# display_board.net
KiCad netlist of a schematic drawn in EasyEDA
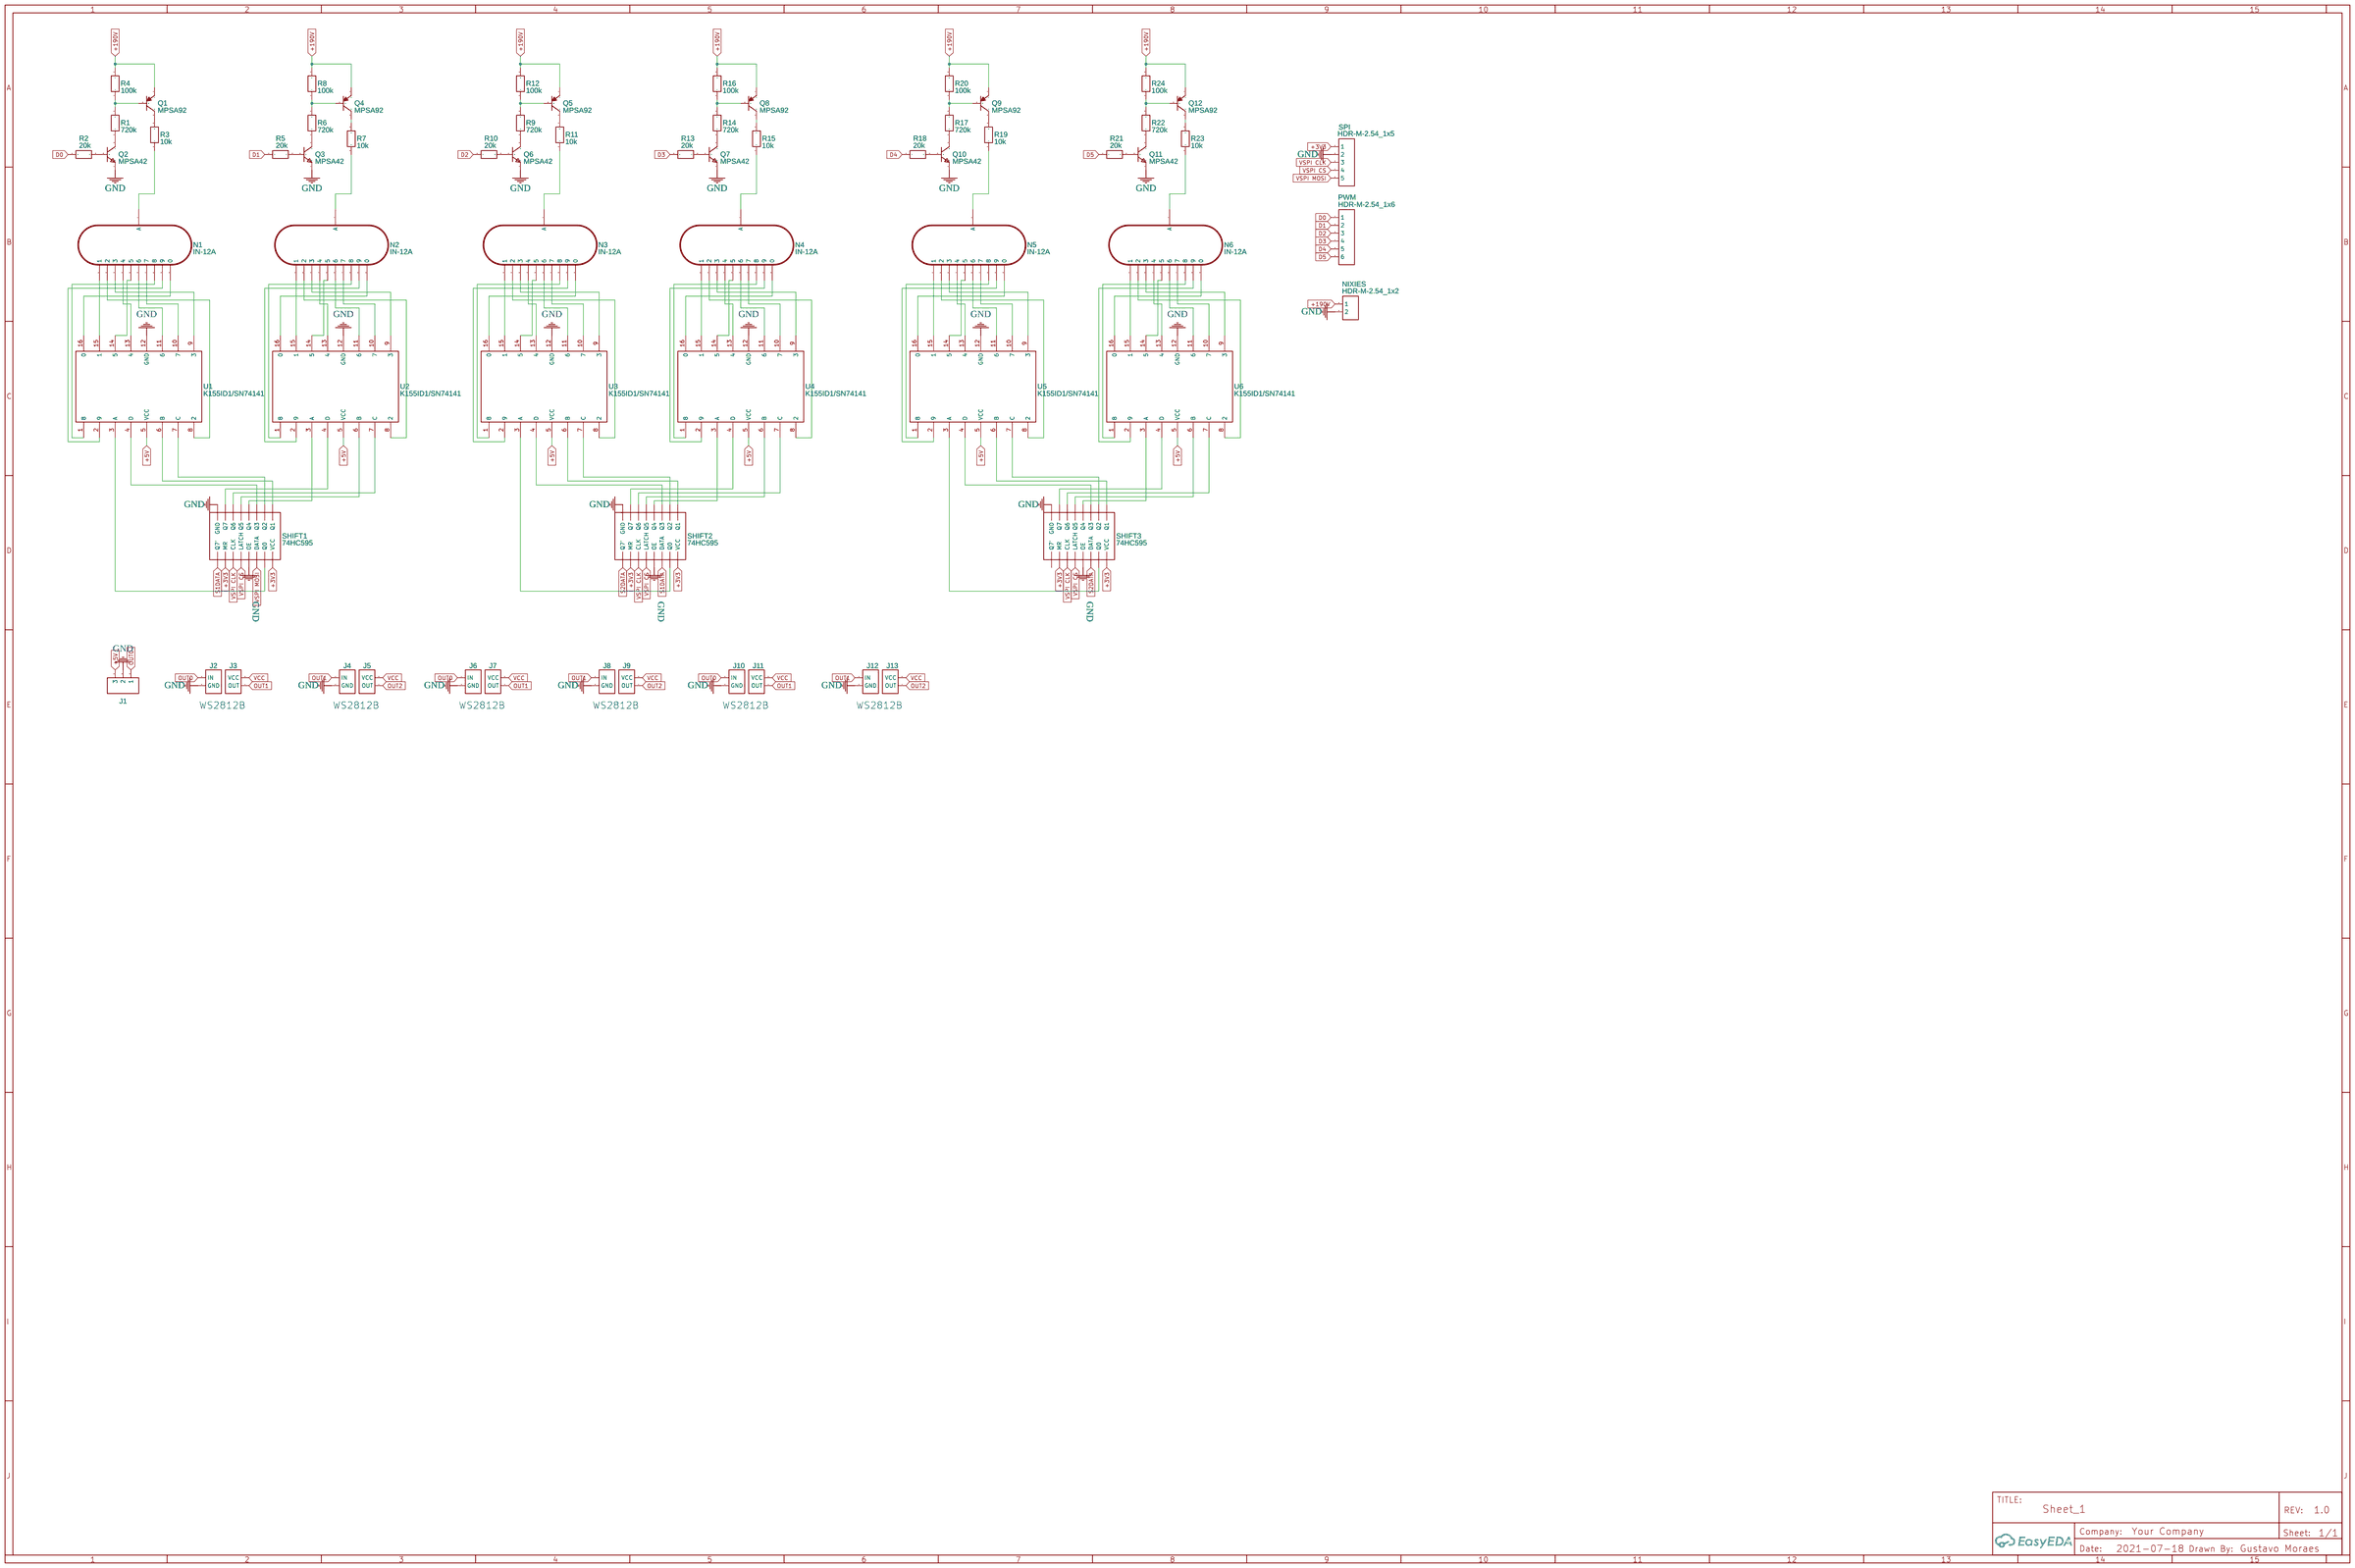
[diagram p0: schematic sheet]

(export (version "E")
  (design (tool "Eeschema 10.0.6"))
  (components
    (comp (ref "J1")
      (value "HDR-M-2.54_1x3")
      (fields (field (name "BOM_Supplier Part") "C180248"))
      (libsource (lib "") (part "HDR-M-2.54_1x3"))
    )
    (comp (ref "J2")
      (value "HDR-M-2.54_1x2")
      (fields (field (name "BOM_Supplier Part") "C124375"))
      (libsource (lib "") (part "HDR-M-2.54_1x2"))
    )
    (comp (ref "J3")
      (value "HDR-M-2.54_1x2")
      (fields (field (name "BOM_Supplier Part") "C124375"))
      (libsource (lib "") (part "HDR-M-2.54_1x2_1"))
    )
    (comp (ref "J4")
      (value "HDR-M-2.54_1x2")
      (fields (field (name "BOM_Supplier Part") "C124375"))
      (libsource (lib "") (part "HDR-M-2.54_1x2"))
    )
    (comp (ref "J5")
      (value "HDR-M-2.54_1x2")
      (fields (field (name "BOM_Supplier Part") "C124375"))
      (libsource (lib "") (part "HDR-M-2.54_1x2_1"))
    )
    (comp (ref "J6")
      (value "HDR-M-2.54_1x2")
      (fields (field (name "BOM_Supplier Part") "C124375"))
      (libsource (lib "") (part "HDR-M-2.54_1x2"))
    )
    (comp (ref "J7")
      (value "HDR-M-2.54_1x2")
      (fields (field (name "BOM_Supplier Part") "C124375"))
      (libsource (lib "") (part "HDR-M-2.54_1x2_1"))
    )
    (comp (ref "J8")
      (value "HDR-M-2.54_1x2")
      (fields (field (name "BOM_Supplier Part") "C124375"))
      (libsource (lib "") (part "HDR-M-2.54_1x2"))
    )
    (comp (ref "J9")
      (value "HDR-M-2.54_1x2")
      (fields (field (name "BOM_Supplier Part") "C124375"))
      (libsource (lib "") (part "HDR-M-2.54_1x2_1"))
    )
    (comp (ref "J10")
      (value "HDR-M-2.54_1x2")
      (fields (field (name "BOM_Supplier Part") "C124375"))
      (libsource (lib "") (part "HDR-M-2.54_1x2"))
    )
    (comp (ref "J11")
      (value "HDR-M-2.54_1x2")
      (fields (field (name "BOM_Supplier Part") "C124375"))
      (libsource (lib "") (part "HDR-M-2.54_1x2_1"))
    )
    (comp (ref "J12")
      (value "HDR-M-2.54_1x2")
      (fields (field (name "BOM_Supplier Part") "C124375"))
      (libsource (lib "") (part "HDR-M-2.54_1x2"))
    )
    (comp (ref "J13")
      (value "HDR-M-2.54_1x2")
      (fields (field (name "BOM_Supplier Part") "C124375"))
      (libsource (lib "") (part "HDR-M-2.54_1x2_1"))
    )
    (comp (ref "N1") (value "IN-12A") (libsource (lib "") (part "IN-12A")))
    (comp (ref "N2") (value "IN-12A") (libsource (lib "") (part "IN-12A")))
    (comp (ref "N3") (value "IN-12A") (libsource (lib "") (part "IN-12A")))
    (comp (ref "N4") (value "IN-12A") (libsource (lib "") (part "IN-12A")))
    (comp (ref "N5") (value "IN-12A") (libsource (lib "") (part "IN-12A")))
    (comp (ref "N6") (value "IN-12A") (libsource (lib "") (part "IN-12A")))
    (comp (ref "NIXIES")
      (value "HDR-M-2.54_1x2")
      (fields (field (name "BOM_Supplier Part") "C124375"))
      (libsource (lib "") (part "HDR-M-2.54_1x2_2"))
    )
    (comp (ref "PWM")
      (value "HDR-M-2.54_1x6")
      (fields (field (name "BOM_Supplier Part") "C190819"))
      (libsource (lib "") (part "HDR-M-2.54_1x6"))
    )
    (comp (ref "Q1")
      (value "MPSA92")
      (fields (field (name "BOM_Supplier Part") "C118558"))
      (libsource (lib "") (part "MPSA92"))
    )
    (comp (ref "Q2")
      (value "MPSA42")
      (fields (field (name "BOM_Supplier Part") "C118557"))
      (libsource (lib "") (part "MPSA42"))
    )
    (comp (ref "Q3")
      (value "MPSA42")
      (fields (field (name "BOM_Supplier Part") "C118557"))
      (libsource (lib "") (part "MPSA42"))
    )
    (comp (ref "Q4")
      (value "MPSA92")
      (fields (field (name "BOM_Supplier Part") "C118558"))
      (libsource (lib "") (part "MPSA92"))
    )
    (comp (ref "Q5")
      (value "MPSA92")
      (fields (field (name "BOM_Supplier Part") "C118558"))
      (libsource (lib "") (part "MPSA92"))
    )
    (comp (ref "Q6")
      (value "MPSA42")
      (fields (field (name "BOM_Supplier Part") "C118557"))
      (libsource (lib "") (part "MPSA42"))
    )
    (comp (ref "Q7")
      (value "MPSA42")
      (fields (field (name "BOM_Supplier Part") "C118557"))
      (libsource (lib "") (part "MPSA42"))
    )
    (comp (ref "Q8")
      (value "MPSA92")
      (fields (field (name "BOM_Supplier Part") "C118558"))
      (libsource (lib "") (part "MPSA92"))
    )
    (comp (ref "Q9")
      (value "MPSA92")
      (fields (field (name "BOM_Supplier Part") "C118558"))
      (libsource (lib "") (part "MPSA92"))
    )
    (comp (ref "Q10")
      (value "MPSA42")
      (fields (field (name "BOM_Supplier Part") "C118557"))
      (libsource (lib "") (part "MPSA42"))
    )
    (comp (ref "Q11")
      (value "MPSA42")
      (fields (field (name "BOM_Supplier Part") "C118557"))
      (libsource (lib "") (part "MPSA42"))
    )
    (comp (ref "Q12")
      (value "MPSA92")
      (fields (field (name "BOM_Supplier Part") "C118558"))
      (libsource (lib "") (part "MPSA92"))
    )
    (comp (ref "R1") (value "720k") (libsource (lib "") (part "R_AXIAL-0.3_EU")))
    (comp (ref "R2") (value "20k") (libsource (lib "") (part "R_AXIAL-0.3_EU_1")))
    (comp (ref "R3") (value "10k") (libsource (lib "") (part "R_AXIAL-0.3_EU")))
    (comp (ref "R4") (value "100k") (libsource (lib "") (part "R_AXIAL-0.3_EU")))
    (comp (ref "R5") (value "20k") (libsource (lib "") (part "R_AXIAL-0.3_EU_1")))
    (comp (ref "R6") (value "720k") (libsource (lib "") (part "R_AXIAL-0.3_EU")))
    (comp (ref "R7") (value "10k") (libsource (lib "") (part "R_AXIAL-0.3_EU")))
    (comp (ref "R8") (value "100k") (libsource (lib "") (part "R_AXIAL-0.3_EU")))
    (comp (ref "R9") (value "720k") (libsource (lib "") (part "R_AXIAL-0.3_EU")))
    (comp (ref "R10") (value "20k") (libsource (lib "") (part "R_AXIAL-0.3_EU_1")))
    (comp (ref "R11") (value "10k") (libsource (lib "") (part "R_AXIAL-0.3_EU")))
    (comp (ref "R12") (value "100k") (libsource (lib "") (part "R_AXIAL-0.3_EU")))
    (comp (ref "R13") (value "20k") (libsource (lib "") (part "R_AXIAL-0.3_EU_1")))
    (comp (ref "R14") (value "720k") (libsource (lib "") (part "R_AXIAL-0.3_EU")))
    (comp (ref "R15") (value "10k") (libsource (lib "") (part "R_AXIAL-0.3_EU")))
    (comp (ref "R16") (value "100k") (libsource (lib "") (part "R_AXIAL-0.3_EU")))
    (comp (ref "R17") (value "720k") (libsource (lib "") (part "R_AXIAL-0.3_EU")))
    (comp (ref "R18") (value "20k") (libsource (lib "") (part "R_AXIAL-0.3_EU_1")))
    (comp (ref "R19") (value "10k") (libsource (lib "") (part "R_AXIAL-0.3_EU")))
    (comp (ref "R20") (value "100k") (libsource (lib "") (part "R_AXIAL-0.3_EU")))
    (comp (ref "R21") (value "20k") (libsource (lib "") (part "R_AXIAL-0.3_EU_1")))
    (comp (ref "R22") (value "720k") (libsource (lib "") (part "R_AXIAL-0.3_EU")))
    (comp (ref "R23") (value "10k") (libsource (lib "") (part "R_AXIAL-0.3_EU")))
    (comp (ref "R24") (value "100k") (libsource (lib "") (part "R_AXIAL-0.3_EU")))
    (comp (ref "SHIFT1") (value "74HC595") (libsource (lib "") (part "74HC595")))
    (comp (ref "SHIFT2") (value "74HC595") (libsource (lib "") (part "74HC595")))
    (comp (ref "SHIFT3") (value "74HC595") (libsource (lib "") (part "74HC595")))
    (comp (ref "SPI")
      (value "HDR-M-2.54_1x5")
      (fields (field (name "BOM_Supplier Part") "C358687"))
      (libsource (lib "") (part "HDR-M-2.54_1x5"))
    )
    (comp (ref "U1") (value "K155ID1/SN74141") (libsource (lib "") (part "K155ID1/SN74141")))
    (comp (ref "U2") (value "K155ID1/SN74141") (libsource (lib "") (part "K155ID1/SN74141")))
    (comp (ref "U3") (value "K155ID1/SN74141") (libsource (lib "") (part "K155ID1/SN74141")))
    (comp (ref "U4") (value "K155ID1/SN74141") (libsource (lib "") (part "K155ID1/SN74141")))
    (comp (ref "U5") (value "K155ID1/SN74141") (libsource (lib "") (part "K155ID1/SN74141")))
    (comp (ref "U6") (value "K155ID1/SN74141") (libsource (lib "") (part "K155ID1/SN74141")))
  )
  (nets
    (net (code "1") (name "+3V3") (class "Default")
      (node (ref "SHIFT1") (pin "10") (pinfunction "MR_10") (pintype "unspecified"))
      (node (ref "SHIFT1") (pin "16") (pinfunction "VCC_16") (pintype "unspecified"))
      (node (ref "SHIFT2") (pin "10") (pinfunction "MR_10") (pintype "unspecified"))
      (node (ref "SHIFT2") (pin "16") (pinfunction "VCC_16") (pintype "unspecified"))
      (node (ref "SHIFT3") (pin "10") (pinfunction "MR_10") (pintype "unspecified"))
      (node (ref "SHIFT3") (pin "16") (pinfunction "VCC_16") (pintype "unspecified"))
      (node (ref "SPI") (pin "1") (pinfunction "1_1") (pintype "unspecified"))
    )
    (net (code "2") (name "+5V") (class "Default")
      (node (ref "J1") (pin "3") (pinfunction "3_3") (pintype "input"))
      (node (ref "U1") (pin "5") (pinfunction "VCC_5") (pintype "unspecified"))
      (node (ref "U2") (pin "5") (pinfunction "VCC_5") (pintype "unspecified"))
      (node (ref "U3") (pin "5") (pinfunction "VCC_5") (pintype "unspecified"))
      (node (ref "U4") (pin "5") (pinfunction "VCC_5") (pintype "unspecified"))
      (node (ref "U5") (pin "5") (pinfunction "VCC_5") (pintype "unspecified"))
      (node (ref "U6") (pin "5") (pinfunction "VCC_5") (pintype "unspecified"))
    )
    (net (code "3") (name "+190V") (class "Default")
      (node (ref "NIXIES") (pin "1") (pinfunction "1_1") (pintype "unspecified"))
      (node (ref "Q1") (pin "1") (pinfunction "1_1") (pintype "input"))
      (node (ref "Q12") (pin "1") (pinfunction "1_1") (pintype "input"))
      (node (ref "Q4") (pin "1") (pinfunction "1_1") (pintype "input"))
      (node (ref "Q5") (pin "1") (pinfunction "1_1") (pintype "input"))
      (node (ref "Q8") (pin "1") (pinfunction "1_1") (pintype "input"))
      (node (ref "Q9") (pin "1") (pinfunction "1_1") (pintype "input"))
      (node (ref "R12") (pin "2") (pinfunction "2_2") (pintype "unspecified"))
      (node (ref "R16") (pin "2") (pinfunction "2_2") (pintype "unspecified"))
      (node (ref "R20") (pin "2") (pinfunction "2_2") (pintype "unspecified"))
      (node (ref "R24") (pin "2") (pinfunction "2_2") (pintype "unspecified"))
      (node (ref "R4") (pin "2") (pinfunction "2_2") (pintype "unspecified"))
      (node (ref "R8") (pin "2") (pinfunction "2_2") (pintype "unspecified"))
    )
    (net (code "4") (name "D0") (class "Default")
      (node (ref "PWM") (pin "1") (pinfunction "1_1") (pintype "input"))
      (node (ref "R2") (pin "1") (pinfunction "1_1") (pintype "unspecified"))
    )
    (net (code "5") (name "D1") (class "Default")
      (node (ref "PWM") (pin "2") (pinfunction "2_2") (pintype "input"))
      (node (ref "R5") (pin "1") (pinfunction "1_1") (pintype "unspecified"))
    )
    (net (code "6") (name "D2") (class "Default")
      (node (ref "PWM") (pin "3") (pinfunction "3_3") (pintype "input"))
      (node (ref "R10") (pin "1") (pinfunction "1_1") (pintype "unspecified"))
    )
    (net (code "7") (name "D3") (class "Default")
      (node (ref "PWM") (pin "4") (pinfunction "4_4") (pintype "input"))
      (node (ref "R13") (pin "1") (pinfunction "1_1") (pintype "unspecified"))
    )
    (net (code "8") (name "D4") (class "Default")
      (node (ref "PWM") (pin "5") (pinfunction "5_5") (pintype "input"))
      (node (ref "R18") (pin "1") (pinfunction "1_1") (pintype "unspecified"))
    )
    (net (code "9") (name "D5") (class "Default")
      (node (ref "PWM") (pin "6") (pinfunction "6_6") (pintype "input"))
      (node (ref "R21") (pin "1") (pinfunction "1_1") (pintype "unspecified"))
    )
    (net (code "10") (name "GND") (class "Default")
      (node (ref "J1") (pin "2") (pinfunction "2_2") (pintype "input"))
      (node (ref "J10") (pin "2") (pinfunction "GND_2") (pintype "unspecified"))
      (node (ref "J12") (pin "2") (pinfunction "GND_2") (pintype "unspecified"))
      (node (ref "J2") (pin "2") (pinfunction "GND_2") (pintype "unspecified"))
      (node (ref "J4") (pin "2") (pinfunction "GND_2") (pintype "unspecified"))
      (node (ref "J6") (pin "2") (pinfunction "GND_2") (pintype "unspecified"))
      (node (ref "J8") (pin "2") (pinfunction "GND_2") (pintype "unspecified"))
      (node (ref "NIXIES") (pin "2") (pinfunction "2_2") (pintype "unspecified"))
      (node (ref "Q10") (pin "1") (pinfunction "E_1") (pintype "unspecified"))
      (node (ref "Q11") (pin "1") (pinfunction "E_1") (pintype "unspecified"))
      (node (ref "Q2") (pin "1") (pinfunction "E_1") (pintype "unspecified"))
      (node (ref "Q3") (pin "1") (pinfunction "E_1") (pintype "unspecified"))
      (node (ref "Q6") (pin "1") (pinfunction "E_1") (pintype "unspecified"))
      (node (ref "Q7") (pin "1") (pinfunction "E_1") (pintype "unspecified"))
      (node (ref "SHIFT1") (pin "13") (pinfunction "OE_13") (pintype "unspecified"))
      (node (ref "SHIFT1") (pin "8") (pinfunction "GND_8") (pintype "unspecified"))
      (node (ref "SHIFT2") (pin "13") (pinfunction "OE_13") (pintype "unspecified"))
      (node (ref "SHIFT2") (pin "8") (pinfunction "GND_8") (pintype "unspecified"))
      (node (ref "SHIFT3") (pin "13") (pinfunction "OE_13") (pintype "unspecified"))
      (node (ref "SHIFT3") (pin "8") (pinfunction "GND_8") (pintype "unspecified"))
      (node (ref "SPI") (pin "2") (pinfunction "2_2") (pintype "unspecified"))
      (node (ref "U1") (pin "12") (pinfunction "GND_12") (pintype "unspecified"))
      (node (ref "U2") (pin "12") (pinfunction "GND_12") (pintype "unspecified"))
      (node (ref "U3") (pin "12") (pinfunction "GND_12") (pintype "unspecified"))
      (node (ref "U4") (pin "12") (pinfunction "GND_12") (pintype "unspecified"))
      (node (ref "U5") (pin "12") (pinfunction "GND_12") (pintype "unspecified"))
      (node (ref "U6") (pin "12") (pinfunction "GND_12") (pintype "unspecified"))
    )
    (net (code "11") (name "Net-(N1-PadA)") (class "Default")
      (node (ref "N1") (pin "A") (pinfunction "A_A") (pintype "unspecified"))
      (node (ref "R3") (pin "1") (pinfunction "1_1") (pintype "unspecified"))
    )
    (net (code "12") (name "Net-(N2-PadA)") (class "Default")
      (node (ref "N2") (pin "A") (pinfunction "A_A") (pintype "unspecified"))
      (node (ref "R7") (pin "1") (pinfunction "1_1") (pintype "unspecified"))
    )
    (net (code "13") (name "Net-(N3-PadA)") (class "Default")
      (node (ref "N3") (pin "A") (pinfunction "A_A") (pintype "unspecified"))
      (node (ref "R11") (pin "1") (pinfunction "1_1") (pintype "unspecified"))
    )
    (net (code "14") (name "Net-(N4-PadA)") (class "Default")
      (node (ref "N4") (pin "A") (pinfunction "A_A") (pintype "unspecified"))
      (node (ref "R15") (pin "1") (pinfunction "1_1") (pintype "unspecified"))
    )
    (net (code "15") (name "Net-(N5-PadA)") (class "Default")
      (node (ref "N5") (pin "A") (pinfunction "A_A") (pintype "unspecified"))
      (node (ref "R19") (pin "1") (pinfunction "1_1") (pintype "unspecified"))
    )
    (net (code "16") (name "Net-(N6-PadA)") (class "Default")
      (node (ref "N6") (pin "A") (pinfunction "A_A") (pintype "unspecified"))
      (node (ref "R23") (pin "1") (pinfunction "1_1") (pintype "unspecified"))
    )
    (net (code "17") (name "Net-(Q1-Pad2)") (class "Default")
      (node (ref "Q1") (pin "2") (pinfunction "2_2") (pintype "input"))
      (node (ref "R1") (pin "2") (pinfunction "2_2") (pintype "unspecified"))
      (node (ref "R4") (pin "1") (pinfunction "1_1") (pintype "unspecified"))
    )
    (net (code "18") (name "Net-(Q1-Pad3)") (class "Default")
      (node (ref "Q1") (pin "3") (pinfunction "3_3") (pintype "input"))
      (node (ref "R3") (pin "2") (pinfunction "2_2") (pintype "unspecified"))
    )
    (net (code "19") (name "Net-(Q2-B)") (class "Default")
      (node (ref "Q2") (pin "2") (pinfunction "B_2") (pintype "unspecified"))
      (node (ref "R2") (pin "2") (pinfunction "2_2") (pintype "unspecified"))
    )
    (net (code "20") (name "Net-(Q2-C)") (class "Default")
      (node (ref "Q2") (pin "3") (pinfunction "C_3") (pintype "unspecified"))
      (node (ref "R1") (pin "1") (pinfunction "1_1") (pintype "unspecified"))
    )
    (net (code "21") (name "Net-(Q3-B)") (class "Default")
      (node (ref "Q3") (pin "2") (pinfunction "B_2") (pintype "unspecified"))
      (node (ref "R5") (pin "2") (pinfunction "2_2") (pintype "unspecified"))
    )
    (net (code "22") (name "Net-(Q3-C)") (class "Default")
      (node (ref "Q3") (pin "3") (pinfunction "C_3") (pintype "unspecified"))
      (node (ref "R6") (pin "1") (pinfunction "1_1") (pintype "unspecified"))
    )
    (net (code "23") (name "Net-(Q4-Pad2)") (class "Default")
      (node (ref "Q4") (pin "2") (pinfunction "2_2") (pintype "input"))
      (node (ref "R6") (pin "2") (pinfunction "2_2") (pintype "unspecified"))
      (node (ref "R8") (pin "1") (pinfunction "1_1") (pintype "unspecified"))
    )
    (net (code "24") (name "Net-(Q4-Pad3)") (class "Default")
      (node (ref "Q4") (pin "3") (pinfunction "3_3") (pintype "input"))
      (node (ref "R7") (pin "2") (pinfunction "2_2") (pintype "unspecified"))
    )
    (net (code "25") (name "Net-(Q5-Pad2)") (class "Default")
      (node (ref "Q5") (pin "2") (pinfunction "2_2") (pintype "input"))
      (node (ref "R12") (pin "1") (pinfunction "1_1") (pintype "unspecified"))
      (node (ref "R9") (pin "2") (pinfunction "2_2") (pintype "unspecified"))
    )
    (net (code "26") (name "Net-(Q5-Pad3)") (class "Default")
      (node (ref "Q5") (pin "3") (pinfunction "3_3") (pintype "input"))
      (node (ref "R11") (pin "2") (pinfunction "2_2") (pintype "unspecified"))
    )
    (net (code "27") (name "Net-(Q6-B)") (class "Default")
      (node (ref "Q6") (pin "2") (pinfunction "B_2") (pintype "unspecified"))
      (node (ref "R10") (pin "2") (pinfunction "2_2") (pintype "unspecified"))
    )
    (net (code "28") (name "Net-(Q6-C)") (class "Default")
      (node (ref "Q6") (pin "3") (pinfunction "C_3") (pintype "unspecified"))
      (node (ref "R9") (pin "1") (pinfunction "1_1") (pintype "unspecified"))
    )
    (net (code "29") (name "Net-(Q7-B)") (class "Default")
      (node (ref "Q7") (pin "2") (pinfunction "B_2") (pintype "unspecified"))
      (node (ref "R13") (pin "2") (pinfunction "2_2") (pintype "unspecified"))
    )
    (net (code "30") (name "Net-(Q7-C)") (class "Default")
      (node (ref "Q7") (pin "3") (pinfunction "C_3") (pintype "unspecified"))
      (node (ref "R14") (pin "1") (pinfunction "1_1") (pintype "unspecified"))
    )
    (net (code "31") (name "Net-(Q8-Pad2)") (class "Default")
      (node (ref "Q8") (pin "2") (pinfunction "2_2") (pintype "input"))
      (node (ref "R14") (pin "2") (pinfunction "2_2") (pintype "unspecified"))
      (node (ref "R16") (pin "1") (pinfunction "1_1") (pintype "unspecified"))
    )
    (net (code "32") (name "Net-(Q8-Pad3)") (class "Default")
      (node (ref "Q8") (pin "3") (pinfunction "3_3") (pintype "input"))
      (node (ref "R15") (pin "2") (pinfunction "2_2") (pintype "unspecified"))
    )
    (net (code "33") (name "Net-(Q9-Pad2)") (class "Default")
      (node (ref "Q9") (pin "2") (pinfunction "2_2") (pintype "input"))
      (node (ref "R17") (pin "2") (pinfunction "2_2") (pintype "unspecified"))
      (node (ref "R20") (pin "1") (pinfunction "1_1") (pintype "unspecified"))
    )
    (net (code "34") (name "Net-(Q9-Pad3)") (class "Default")
      (node (ref "Q9") (pin "3") (pinfunction "3_3") (pintype "input"))
      (node (ref "R19") (pin "2") (pinfunction "2_2") (pintype "unspecified"))
    )
    (net (code "35") (name "Net-(Q10-B)") (class "Default")
      (node (ref "Q10") (pin "2") (pinfunction "B_2") (pintype "unspecified"))
      (node (ref "R18") (pin "2") (pinfunction "2_2") (pintype "unspecified"))
    )
    (net (code "36") (name "Net-(Q10-C)") (class "Default")
      (node (ref "Q10") (pin "3") (pinfunction "C_3") (pintype "unspecified"))
      (node (ref "R17") (pin "1") (pinfunction "1_1") (pintype "unspecified"))
    )
    (net (code "37") (name "Net-(Q11-B)") (class "Default")
      (node (ref "Q11") (pin "2") (pinfunction "B_2") (pintype "unspecified"))
      (node (ref "R21") (pin "2") (pinfunction "2_2") (pintype "unspecified"))
    )
    (net (code "38") (name "Net-(Q11-C)") (class "Default")
      (node (ref "Q11") (pin "3") (pinfunction "C_3") (pintype "unspecified"))
      (node (ref "R22") (pin "1") (pinfunction "1_1") (pintype "unspecified"))
    )
    (net (code "39") (name "Net-(Q12-Pad2)") (class "Default")
      (node (ref "Q12") (pin "2") (pinfunction "2_2") (pintype "input"))
      (node (ref "R22") (pin "2") (pinfunction "2_2") (pintype "unspecified"))
      (node (ref "R24") (pin "1") (pinfunction "1_1") (pintype "unspecified"))
    )
    (net (code "40") (name "Net-(Q12-Pad3)") (class "Default")
      (node (ref "Q12") (pin "3") (pinfunction "3_3") (pintype "input"))
      (node (ref "R23") (pin "2") (pinfunction "2_2") (pintype "unspecified"))
    )
    (net (code "41") (name "Net-(SHIFT1-Q0)") (class "Default")
      (node (ref "SHIFT1") (pin "15") (pinfunction "Q0_15") (pintype "unspecified"))
      (node (ref "U1") (pin "3") (pinfunction "A_3") (pintype "unspecified"))
    )
    (net (code "42") (name "Net-(SHIFT1-Q1)") (class "Default")
      (node (ref "SHIFT1") (pin "1") (pinfunction "Q1_1") (pintype "unspecified"))
      (node (ref "U1") (pin "6") (pinfunction "B_6") (pintype "unspecified"))
    )
    (net (code "43") (name "Net-(SHIFT1-Q2)") (class "Default")
      (node (ref "SHIFT1") (pin "2") (pinfunction "Q2_2") (pintype "unspecified"))
      (node (ref "U1") (pin "7") (pinfunction "C_7") (pintype "unspecified"))
    )
    (net (code "44") (name "Net-(SHIFT1-Q3)") (class "Default")
      (node (ref "SHIFT1") (pin "3") (pinfunction "Q3_3") (pintype "unspecified"))
      (node (ref "U1") (pin "4") (pinfunction "D_4") (pintype "unspecified"))
    )
    (net (code "45") (name "Net-(SHIFT1-Q4)") (class "Default")
      (node (ref "SHIFT1") (pin "4") (pinfunction "Q4_4") (pintype "unspecified"))
      (node (ref "U2") (pin "3") (pinfunction "A_3") (pintype "unspecified"))
    )
    (net (code "46") (name "Net-(SHIFT1-Q5)") (class "Default")
      (node (ref "SHIFT1") (pin "5") (pinfunction "Q5_5") (pintype "unspecified"))
      (node (ref "U2") (pin "6") (pinfunction "B_6") (pintype "unspecified"))
    )
    (net (code "47") (name "Net-(SHIFT1-Q6)") (class "Default")
      (node (ref "SHIFT1") (pin "6") (pinfunction "Q6_6") (pintype "unspecified"))
      (node (ref "U2") (pin "7") (pinfunction "C_7") (pintype "unspecified"))
    )
    (net (code "48") (name "Net-(SHIFT1-Q7)") (class "Default")
      (node (ref "SHIFT1") (pin "7") (pinfunction "Q7_7") (pintype "unspecified"))
      (node (ref "U2") (pin "4") (pinfunction "D_4") (pintype "unspecified"))
    )
    (net (code "49") (name "Net-(SHIFT2-Q0)") (class "Default")
      (node (ref "SHIFT2") (pin "15") (pinfunction "Q0_15") (pintype "unspecified"))
      (node (ref "U3") (pin "3") (pinfunction "A_3") (pintype "unspecified"))
    )
    (net (code "50") (name "Net-(SHIFT2-Q1)") (class "Default")
      (node (ref "SHIFT2") (pin "1") (pinfunction "Q1_1") (pintype "unspecified"))
      (node (ref "U3") (pin "6") (pinfunction "B_6") (pintype "unspecified"))
    )
    (net (code "51") (name "Net-(SHIFT2-Q2)") (class "Default")
      (node (ref "SHIFT2") (pin "2") (pinfunction "Q2_2") (pintype "unspecified"))
      (node (ref "U3") (pin "7") (pinfunction "C_7") (pintype "unspecified"))
    )
    (net (code "52") (name "Net-(SHIFT2-Q3)") (class "Default")
      (node (ref "SHIFT2") (pin "3") (pinfunction "Q3_3") (pintype "unspecified"))
      (node (ref "U3") (pin "4") (pinfunction "D_4") (pintype "unspecified"))
    )
    (net (code "53") (name "Net-(SHIFT2-Q4)") (class "Default")
      (node (ref "SHIFT2") (pin "4") (pinfunction "Q4_4") (pintype "unspecified"))
      (node (ref "U4") (pin "3") (pinfunction "A_3") (pintype "unspecified"))
    )
    (net (code "54") (name "Net-(SHIFT2-Q5)") (class "Default")
      (node (ref "SHIFT2") (pin "5") (pinfunction "Q5_5") (pintype "unspecified"))
      (node (ref "U4") (pin "6") (pinfunction "B_6") (pintype "unspecified"))
    )
    (net (code "55") (name "Net-(SHIFT2-Q6)") (class "Default")
      (node (ref "SHIFT2") (pin "6") (pinfunction "Q6_6") (pintype "unspecified"))
      (node (ref "U4") (pin "7") (pinfunction "C_7") (pintype "unspecified"))
    )
    (net (code "56") (name "Net-(SHIFT2-Q7)") (class "Default")
      (node (ref "SHIFT2") (pin "7") (pinfunction "Q7_7") (pintype "unspecified"))
      (node (ref "U4") (pin "4") (pinfunction "D_4") (pintype "unspecified"))
    )
    (net (code "57") (name "Net-(SHIFT3-Q0)") (class "Default")
      (node (ref "SHIFT3") (pin "15") (pinfunction "Q0_15") (pintype "unspecified"))
      (node (ref "U5") (pin "3") (pinfunction "A_3") (pintype "unspecified"))
    )
    (net (code "58") (name "Net-(SHIFT3-Q1)") (class "Default")
      (node (ref "SHIFT3") (pin "1") (pinfunction "Q1_1") (pintype "unspecified"))
      (node (ref "U5") (pin "6") (pinfunction "B_6") (pintype "unspecified"))
    )
    (net (code "59") (name "Net-(SHIFT3-Q2)") (class "Default")
      (node (ref "SHIFT3") (pin "2") (pinfunction "Q2_2") (pintype "unspecified"))
      (node (ref "U5") (pin "7") (pinfunction "C_7") (pintype "unspecified"))
    )
    (net (code "60") (name "Net-(SHIFT3-Q3)") (class "Default")
      (node (ref "SHIFT3") (pin "3") (pinfunction "Q3_3") (pintype "unspecified"))
      (node (ref "U5") (pin "4") (pinfunction "D_4") (pintype "unspecified"))
    )
    (net (code "61") (name "Net-(SHIFT3-Q4)") (class "Default")
      (node (ref "SHIFT3") (pin "4") (pinfunction "Q4_4") (pintype "unspecified"))
      (node (ref "U6") (pin "3") (pinfunction "A_3") (pintype "unspecified"))
    )
    (net (code "62") (name "Net-(SHIFT3-Q5)") (class "Default")
      (node (ref "SHIFT3") (pin "5") (pinfunction "Q5_5") (pintype "unspecified"))
      (node (ref "U6") (pin "6") (pinfunction "B_6") (pintype "unspecified"))
    )
    (net (code "63") (name "Net-(SHIFT3-Q6)") (class "Default")
      (node (ref "SHIFT3") (pin "6") (pinfunction "Q6_6") (pintype "unspecified"))
      (node (ref "U6") (pin "7") (pinfunction "C_7") (pintype "unspecified"))
    )
    (net (code "64") (name "Net-(SHIFT3-Q7)") (class "Default")
      (node (ref "SHIFT3") (pin "7") (pinfunction "Q7_7") (pintype "unspecified"))
      (node (ref "U6") (pin "4") (pinfunction "D_4") (pintype "unspecified"))
    )
    (net (code "65") (name "Net-(U1-0)") (class "Default")
      (node (ref "N1") (pin "0") (pinfunction "0_0") (pintype "unspecified"))
      (node (ref "U1") (pin "16") (pinfunction "0_16") (pintype "unspecified"))
    )
    (net (code "66") (name "Net-(U1-1)") (class "Default")
      (node (ref "N1") (pin "1") (pinfunction "1_1") (pintype "unspecified"))
      (node (ref "U1") (pin "15") (pinfunction "1_15") (pintype "unspecified"))
    )
    (net (code "67") (name "Net-(U1-2)") (class "Default")
      (node (ref "N1") (pin "2") (pinfunction "2_2") (pintype "unspecified"))
      (node (ref "U1") (pin "8") (pinfunction "2_8") (pintype "unspecified"))
    )
    (net (code "68") (name "Net-(U1-3)") (class "Default")
      (node (ref "N1") (pin "3") (pinfunction "3_3") (pintype "unspecified"))
      (node (ref "U1") (pin "9") (pinfunction "3_9") (pintype "unspecified"))
    )
    (net (code "69") (name "Net-(U1-4)") (class "Default")
      (node (ref "N1") (pin "4") (pinfunction "4_4") (pintype "unspecified"))
      (node (ref "U1") (pin "13") (pinfunction "4_13") (pintype "unspecified"))
    )
    (net (code "70") (name "Net-(U1-5)") (class "Default")
      (node (ref "N1") (pin "5") (pinfunction "5_5") (pintype "unspecified"))
      (node (ref "U1") (pin "14") (pinfunction "5_14") (pintype "unspecified"))
    )
    (net (code "71") (name "Net-(U1-6)") (class "Default")
      (node (ref "N1") (pin "6") (pinfunction "6_6") (pintype "unspecified"))
      (node (ref "U1") (pin "11") (pinfunction "6_11") (pintype "unspecified"))
    )
    (net (code "72") (name "Net-(U1-7)") (class "Default")
      (node (ref "N1") (pin "7") (pinfunction "7_7") (pintype "unspecified"))
      (node (ref "U1") (pin "10") (pinfunction "7_10") (pintype "unspecified"))
    )
    (net (code "73") (name "Net-(U1-8)") (class "Default")
      (node (ref "N1") (pin "8") (pinfunction "8_8") (pintype "unspecified"))
      (node (ref "U1") (pin "1") (pinfunction "8_1") (pintype "unspecified"))
    )
    (net (code "74") (name "Net-(U1-9)") (class "Default")
      (node (ref "N1") (pin "9") (pinfunction "9_9") (pintype "unspecified"))
      (node (ref "U1") (pin "2") (pinfunction "9_2") (pintype "unspecified"))
    )
    (net (code "75") (name "Net-(U2-0)") (class "Default")
      (node (ref "N2") (pin "0") (pinfunction "0_0") (pintype "unspecified"))
      (node (ref "U2") (pin "16") (pinfunction "0_16") (pintype "unspecified"))
    )
    (net (code "76") (name "Net-(U2-1)") (class "Default")
      (node (ref "N2") (pin "1") (pinfunction "1_1") (pintype "unspecified"))
      (node (ref "U2") (pin "15") (pinfunction "1_15") (pintype "unspecified"))
    )
    (net (code "77") (name "Net-(U2-2)") (class "Default")
      (node (ref "N2") (pin "2") (pinfunction "2_2") (pintype "unspecified"))
      (node (ref "U2") (pin "8") (pinfunction "2_8") (pintype "unspecified"))
    )
    (net (code "78") (name "Net-(U2-3)") (class "Default")
      (node (ref "N2") (pin "3") (pinfunction "3_3") (pintype "unspecified"))
      (node (ref "U2") (pin "9") (pinfunction "3_9") (pintype "unspecified"))
    )
    (net (code "79") (name "Net-(U2-4)") (class "Default")
      (node (ref "N2") (pin "4") (pinfunction "4_4") (pintype "unspecified"))
      (node (ref "U2") (pin "13") (pinfunction "4_13") (pintype "unspecified"))
    )
    (net (code "80") (name "Net-(U2-5)") (class "Default")
      (node (ref "N2") (pin "5") (pinfunction "5_5") (pintype "unspecified"))
      (node (ref "U2") (pin "14") (pinfunction "5_14") (pintype "unspecified"))
    )
    (net (code "81") (name "Net-(U2-6)") (class "Default")
      (node (ref "N2") (pin "6") (pinfunction "6_6") (pintype "unspecified"))
      (node (ref "U2") (pin "11") (pinfunction "6_11") (pintype "unspecified"))
    )
    (net (code "82") (name "Net-(U2-7)") (class "Default")
      (node (ref "N2") (pin "7") (pinfunction "7_7") (pintype "unspecified"))
      (node (ref "U2") (pin "10") (pinfunction "7_10") (pintype "unspecified"))
    )
    (net (code "83") (name "Net-(U2-8)") (class "Default")
      (node (ref "N2") (pin "8") (pinfunction "8_8") (pintype "unspecified"))
      (node (ref "U2") (pin "1") (pinfunction "8_1") (pintype "unspecified"))
    )
    (net (code "84") (name "Net-(U2-9)") (class "Default")
      (node (ref "N2") (pin "9") (pinfunction "9_9") (pintype "unspecified"))
      (node (ref "U2") (pin "2") (pinfunction "9_2") (pintype "unspecified"))
    )
    (net (code "85") (name "Net-(U3-0)") (class "Default")
      (node (ref "N3") (pin "0") (pinfunction "0_0") (pintype "unspecified"))
      (node (ref "U3") (pin "16") (pinfunction "0_16") (pintype "unspecified"))
    )
    (net (code "86") (name "Net-(U3-1)") (class "Default")
      (node (ref "N3") (pin "1") (pinfunction "1_1") (pintype "unspecified"))
      (node (ref "U3") (pin "15") (pinfunction "1_15") (pintype "unspecified"))
    )
    (net (code "87") (name "Net-(U3-2)") (class "Default")
      (node (ref "N3") (pin "2") (pinfunction "2_2") (pintype "unspecified"))
      (node (ref "U3") (pin "8") (pinfunction "2_8") (pintype "unspecified"))
    )
    (net (code "88") (name "Net-(U3-3)") (class "Default")
      (node (ref "N3") (pin "3") (pinfunction "3_3") (pintype "unspecified"))
      (node (ref "U3") (pin "9") (pinfunction "3_9") (pintype "unspecified"))
    )
    (net (code "89") (name "Net-(U3-4)") (class "Default")
      (node (ref "N3") (pin "4") (pinfunction "4_4") (pintype "unspecified"))
      (node (ref "U3") (pin "13") (pinfunction "4_13") (pintype "unspecified"))
    )
    (net (code "90") (name "Net-(U3-5)") (class "Default")
      (node (ref "N3") (pin "5") (pinfunction "5_5") (pintype "unspecified"))
      (node (ref "U3") (pin "14") (pinfunction "5_14") (pintype "unspecified"))
    )
    (net (code "91") (name "Net-(U3-6)") (class "Default")
      (node (ref "N3") (pin "6") (pinfunction "6_6") (pintype "unspecified"))
      (node (ref "U3") (pin "11") (pinfunction "6_11") (pintype "unspecified"))
    )
    (net (code "92") (name "Net-(U3-7)") (class "Default")
      (node (ref "N3") (pin "7") (pinfunction "7_7") (pintype "unspecified"))
      (node (ref "U3") (pin "10") (pinfunction "7_10") (pintype "unspecified"))
    )
    (net (code "93") (name "Net-(U3-8)") (class "Default")
      (node (ref "N3") (pin "8") (pinfunction "8_8") (pintype "unspecified"))
      (node (ref "U3") (pin "1") (pinfunction "8_1") (pintype "unspecified"))
    )
    (net (code "94") (name "Net-(U3-9)") (class "Default")
      (node (ref "N3") (pin "9") (pinfunction "9_9") (pintype "unspecified"))
      (node (ref "U3") (pin "2") (pinfunction "9_2") (pintype "unspecified"))
    )
    (net (code "95") (name "Net-(U4-0)") (class "Default")
      (node (ref "N4") (pin "0") (pinfunction "0_0") (pintype "unspecified"))
      (node (ref "U4") (pin "16") (pinfunction "0_16") (pintype "unspecified"))
    )
    (net (code "96") (name "Net-(U4-1)") (class "Default")
      (node (ref "N4") (pin "1") (pinfunction "1_1") (pintype "unspecified"))
      (node (ref "U4") (pin "15") (pinfunction "1_15") (pintype "unspecified"))
    )
    (net (code "97") (name "Net-(U4-2)") (class "Default")
      (node (ref "N4") (pin "2") (pinfunction "2_2") (pintype "unspecified"))
      (node (ref "U4") (pin "8") (pinfunction "2_8") (pintype "unspecified"))
    )
    (net (code "98") (name "Net-(U4-3)") (class "Default")
      (node (ref "N4") (pin "3") (pinfunction "3_3") (pintype "unspecified"))
      (node (ref "U4") (pin "9") (pinfunction "3_9") (pintype "unspecified"))
    )
    (net (code "99") (name "Net-(U4-4)") (class "Default")
      (node (ref "N4") (pin "4") (pinfunction "4_4") (pintype "unspecified"))
      (node (ref "U4") (pin "13") (pinfunction "4_13") (pintype "unspecified"))
    )
    (net (code "100") (name "Net-(U4-5)") (class "Default")
      (node (ref "N4") (pin "5") (pinfunction "5_5") (pintype "unspecified"))
      (node (ref "U4") (pin "14") (pinfunction "5_14") (pintype "unspecified"))
    )
    (net (code "101") (name "Net-(U4-6)") (class "Default")
      (node (ref "N4") (pin "6") (pinfunction "6_6") (pintype "unspecified"))
      (node (ref "U4") (pin "11") (pinfunction "6_11") (pintype "unspecified"))
    )
    (net (code "102") (name "Net-(U4-7)") (class "Default")
      (node (ref "N4") (pin "7") (pinfunction "7_7") (pintype "unspecified"))
      (node (ref "U4") (pin "10") (pinfunction "7_10") (pintype "unspecified"))
    )
    (net (code "103") (name "Net-(U4-8)") (class "Default")
      (node (ref "N4") (pin "8") (pinfunction "8_8") (pintype "unspecified"))
      (node (ref "U4") (pin "1") (pinfunction "8_1") (pintype "unspecified"))
    )
    (net (code "104") (name "Net-(U4-9)") (class "Default")
      (node (ref "N4") (pin "9") (pinfunction "9_9") (pintype "unspecified"))
      (node (ref "U4") (pin "2") (pinfunction "9_2") (pintype "unspecified"))
    )
    (net (code "105") (name "Net-(U5-0)") (class "Default")
      (node (ref "N5") (pin "0") (pinfunction "0_0") (pintype "unspecified"))
      (node (ref "U5") (pin "16") (pinfunction "0_16") (pintype "unspecified"))
    )
    (net (code "106") (name "Net-(U5-1)") (class "Default")
      (node (ref "N5") (pin "1") (pinfunction "1_1") (pintype "unspecified"))
      (node (ref "U5") (pin "15") (pinfunction "1_15") (pintype "unspecified"))
    )
    (net (code "107") (name "Net-(U5-2)") (class "Default")
      (node (ref "N5") (pin "2") (pinfunction "2_2") (pintype "unspecified"))
      (node (ref "U5") (pin "8") (pinfunction "2_8") (pintype "unspecified"))
    )
    (net (code "108") (name "Net-(U5-3)") (class "Default")
      (node (ref "N5") (pin "3") (pinfunction "3_3") (pintype "unspecified"))
      (node (ref "U5") (pin "9") (pinfunction "3_9") (pintype "unspecified"))
    )
    (net (code "109") (name "Net-(U5-4)") (class "Default")
      (node (ref "N5") (pin "4") (pinfunction "4_4") (pintype "unspecified"))
      (node (ref "U5") (pin "13") (pinfunction "4_13") (pintype "unspecified"))
    )
    (net (code "110") (name "Net-(U5-5)") (class "Default")
      (node (ref "N5") (pin "5") (pinfunction "5_5") (pintype "unspecified"))
      (node (ref "U5") (pin "14") (pinfunction "5_14") (pintype "unspecified"))
    )
    (net (code "111") (name "Net-(U5-6)") (class "Default")
      (node (ref "N5") (pin "6") (pinfunction "6_6") (pintype "unspecified"))
      (node (ref "U5") (pin "11") (pinfunction "6_11") (pintype "unspecified"))
    )
    (net (code "112") (name "Net-(U5-7)") (class "Default")
      (node (ref "N5") (pin "7") (pinfunction "7_7") (pintype "unspecified"))
      (node (ref "U5") (pin "10") (pinfunction "7_10") (pintype "unspecified"))
    )
    (net (code "113") (name "Net-(U5-8)") (class "Default")
      (node (ref "N5") (pin "8") (pinfunction "8_8") (pintype "unspecified"))
      (node (ref "U5") (pin "1") (pinfunction "8_1") (pintype "unspecified"))
    )
    (net (code "114") (name "Net-(U5-9)") (class "Default")
      (node (ref "N5") (pin "9") (pinfunction "9_9") (pintype "unspecified"))
      (node (ref "U5") (pin "2") (pinfunction "9_2") (pintype "unspecified"))
    )
    (net (code "115") (name "Net-(U6-0)") (class "Default")
      (node (ref "N6") (pin "0") (pinfunction "0_0") (pintype "unspecified"))
      (node (ref "U6") (pin "16") (pinfunction "0_16") (pintype "unspecified"))
    )
    (net (code "116") (name "Net-(U6-1)") (class "Default")
      (node (ref "N6") (pin "1") (pinfunction "1_1") (pintype "unspecified"))
      (node (ref "U6") (pin "15") (pinfunction "1_15") (pintype "unspecified"))
    )
    (net (code "117") (name "Net-(U6-2)") (class "Default")
      (node (ref "N6") (pin "2") (pinfunction "2_2") (pintype "unspecified"))
      (node (ref "U6") (pin "8") (pinfunction "2_8") (pintype "unspecified"))
    )
    (net (code "118") (name "Net-(U6-3)") (class "Default")
      (node (ref "N6") (pin "3") (pinfunction "3_3") (pintype "unspecified"))
      (node (ref "U6") (pin "9") (pinfunction "3_9") (pintype "unspecified"))
    )
    (net (code "119") (name "Net-(U6-4)") (class "Default")
      (node (ref "N6") (pin "4") (pinfunction "4_4") (pintype "unspecified"))
      (node (ref "U6") (pin "13") (pinfunction "4_13") (pintype "unspecified"))
    )
    (net (code "120") (name "Net-(U6-5)") (class "Default")
      (node (ref "N6") (pin "5") (pinfunction "5_5") (pintype "unspecified"))
      (node (ref "U6") (pin "14") (pinfunction "5_14") (pintype "unspecified"))
    )
    (net (code "121") (name "Net-(U6-6)") (class "Default")
      (node (ref "N6") (pin "6") (pinfunction "6_6") (pintype "unspecified"))
      (node (ref "U6") (pin "11") (pinfunction "6_11") (pintype "unspecified"))
    )
    (net (code "122") (name "Net-(U6-7)") (class "Default")
      (node (ref "N6") (pin "7") (pinfunction "7_7") (pintype "unspecified"))
      (node (ref "U6") (pin "10") (pinfunction "7_10") (pintype "unspecified"))
    )
    (net (code "123") (name "Net-(U6-8)") (class "Default")
      (node (ref "N6") (pin "8") (pinfunction "8_8") (pintype "unspecified"))
      (node (ref "U6") (pin "1") (pinfunction "8_1") (pintype "unspecified"))
    )
    (net (code "124") (name "Net-(U6-9)") (class "Default")
      (node (ref "N6") (pin "9") (pinfunction "9_9") (pintype "unspecified"))
      (node (ref "U6") (pin "2") (pinfunction "9_2") (pintype "unspecified"))
    )
    (net (code "125") (name "OUT0") (class "Default")
      (node (ref "J1") (pin "1") (pinfunction "1_1") (pintype "input"))
      (node (ref "J10") (pin "1") (pinfunction "IN_1") (pintype "unspecified"))
      (node (ref "J2") (pin "1") (pinfunction "IN_1") (pintype "unspecified"))
      (node (ref "J6") (pin "1") (pinfunction "IN_1") (pintype "unspecified"))
    )
    (net (code "126") (name "OUT1") (class "Default")
      (node (ref "J11") (pin "1") (pinfunction "OUT_1") (pintype "unspecified"))
      (node (ref "J12") (pin "1") (pinfunction "IN_1") (pintype "unspecified"))
      (node (ref "J3") (pin "1") (pinfunction "OUT_1") (pintype "unspecified"))
      (node (ref "J4") (pin "1") (pinfunction "IN_1") (pintype "unspecified"))
      (node (ref "J7") (pin "1") (pinfunction "OUT_1") (pintype "unspecified"))
      (node (ref "J8") (pin "1") (pinfunction "IN_1") (pintype "unspecified"))
    )
    (net (code "127") (name "OUT2") (class "Default")
      (node (ref "J13") (pin "1") (pinfunction "OUT_1") (pintype "unspecified"))
      (node (ref "J5") (pin "1") (pinfunction "OUT_1") (pintype "unspecified"))
      (node (ref "J9") (pin "1") (pinfunction "OUT_1") (pintype "unspecified"))
    )
    (net (code "128") (name "S1DATA") (class "Default")
      (node (ref "SHIFT1") (pin "9") (pinfunction "Q7'_9") (pintype "unspecified"))
      (node (ref "SHIFT2") (pin "14") (pinfunction "DATA_14") (pintype "unspecified"))
    )
    (net (code "129") (name "S2DATA") (class "Default")
      (node (ref "SHIFT2") (pin "9") (pinfunction "Q7'_9") (pintype "unspecified"))
      (node (ref "SHIFT3") (pin "14") (pinfunction "DATA_14") (pintype "unspecified"))
    )
    (net (code "130") (name "VCC") (class "Default")
      (node (ref "J11") (pin "2") (pinfunction "VCC_2") (pintype "unspecified"))
      (node (ref "J13") (pin "2") (pinfunction "VCC_2") (pintype "unspecified"))
      (node (ref "J3") (pin "2") (pinfunction "VCC_2") (pintype "unspecified"))
      (node (ref "J5") (pin "2") (pinfunction "VCC_2") (pintype "unspecified"))
      (node (ref "J7") (pin "2") (pinfunction "VCC_2") (pintype "unspecified"))
      (node (ref "J9") (pin "2") (pinfunction "VCC_2") (pintype "unspecified"))
    )
    (net (code "131") (name "VSPI CLK") (class "Default")
      (node (ref "SHIFT1") (pin "11") (pinfunction "CLK_11") (pintype "unspecified"))
      (node (ref "SHIFT2") (pin "11") (pinfunction "CLK_11") (pintype "unspecified"))
      (node (ref "SHIFT3") (pin "11") (pinfunction "CLK_11") (pintype "unspecified"))
      (node (ref "SPI") (pin "3") (pinfunction "3_3") (pintype "unspecified"))
    )
    (net (code "132") (name "VSPI CS") (class "Default")
      (node (ref "SHIFT1") (pin "12") (pinfunction "LATCH_12") (pintype "unspecified"))
      (node (ref "SHIFT2") (pin "12") (pinfunction "LATCH_12") (pintype "unspecified"))
      (node (ref "SHIFT3") (pin "12") (pinfunction "LATCH_12") (pintype "unspecified"))
      (node (ref "SPI") (pin "4") (pinfunction "4_4") (pintype "unspecified"))
    )
    (net (code "133") (name "VSPI MOSI") (class "Default")
      (node (ref "SHIFT1") (pin "14") (pinfunction "DATA_14") (pintype "unspecified"))
      (node (ref "SPI") (pin "5") (pinfunction "5_5") (pintype "unspecified"))
    )
    (net (code "134") (name "unconnected-(SHIFT3-Q7'-Pad9)") (class "Default")
      (node (ref "SHIFT3") (pin "9") (pinfunction "Q7'_9") (pintype "unspecified"))
    )
  )
)
